# Connections.net
KiCad netlist of a schematic drawn in Altium Designer
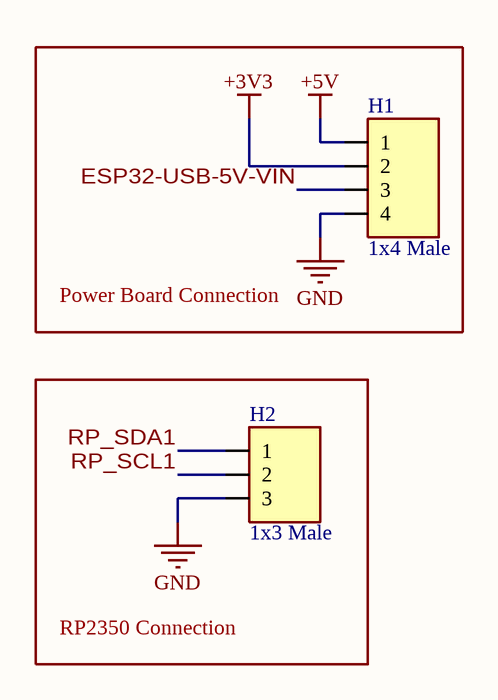
[diagram p0: Connections.SchDoc]

(export (version "E")
  (design (tool "Eeschema 10.0.6"))
  (components
    (comp (ref "H1")
      (value "1x4 Male")
      (footprint "[Header] Shrouded 1x4 Male")
      (description "70543-0003\r\nMates with 005057-9404")
      (libsource (lib "RADM Connectors") (part "[Header] Shrouded 1x4 Male"))
    )
    (comp (ref "H2")
      (value "1x3 Male")
      (footprint "[Header] Shrouded 1x3 Male")
      (description "070543-0037\r\nMates with 005057-9403")
      (libsource (lib "RADM Connectors") (part "[Header] Shrouded 1x3 Male"))
    )
  )
  (nets
    (net (code "1") (name "+3V3") (class "Default")
      (node (ref "H1") (pin "2") (pinfunction "2_2") (pintype "passive"))
    )
    (net (code "2") (name "+5V") (class "Default")
      (node (ref "H1") (pin "1") (pinfunction "1_1") (pintype "passive"))
    )
    (net (code "3") (name "/ESP32-USB-5V-VIN") (class "Default")
      (node (ref "H1") (pin "3") (pinfunction "3_3") (pintype "passive"))
    )
    (net (code "4") (name "/RP_SCL1") (class "Default")
      (node (ref "H2") (pin "2") (pinfunction "2_2") (pintype "passive"))
    )
    (net (code "5") (name "/RP_SDA1") (class "Default")
      (node (ref "H2") (pin "1") (pinfunction "1_1") (pintype "passive"))
    )
    (net (code "6") (name "GND") (class "Default")
      (node (ref "H1") (pin "4") (pinfunction "4_4") (pintype "passive"))
      (node (ref "H2") (pin "3") (pinfunction "3_3") (pintype "passive"))
    )
  )
)
